# KR-51_V56.net
KiCad netlist of a schematic drawn in Altium Designer
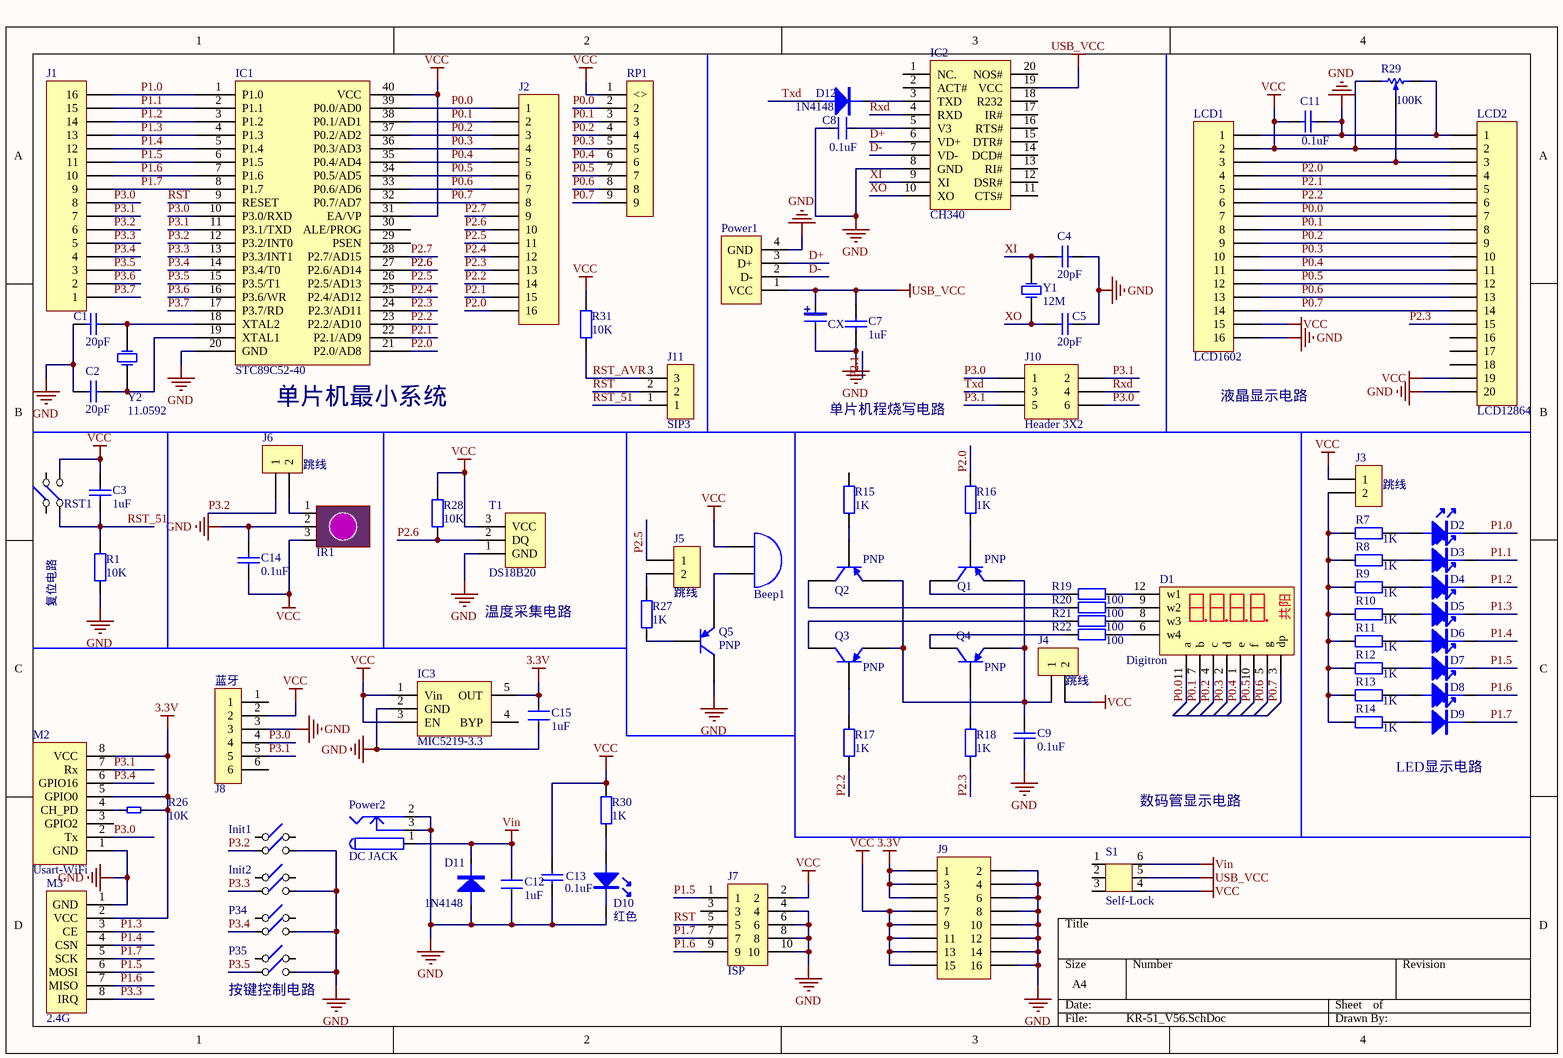
[diagram p0: KR-51_V56.SchDoc]

(export (version "E")
  (design (tool "Eeschema 10.0.6"))
  (components
    (comp (ref "Beep1") (value "蜂鸣器") (footprint "beep") (libsource (lib "声器件") (part "蜂鸣器")))
    (comp (ref "C1")
      (value "20pF")
      (footprint "0805_C")
      (description "Capacitor")
      (fields (field (name "Comment") "Cap_SMT"))
      (libsource (lib "My_Library1") (part "Cap_SMT"))
    )
    (comp (ref "C2")
      (value "20pF")
      (footprint "0805_C")
      (description "Capacitor")
      (fields (field (name "Comment") "Cap_SMT"))
      (libsource (lib "My_Library1") (part "Cap_SMT"))
    )
    (comp (ref "C3")
      (value "1uF")
      (footprint "0805_C")
      (description "Capacitor")
      (fields (field (name "Comment") "Cap_SMT"))
      (libsource (lib "My_Library1") (part "Cap_SMT"))
    )
    (comp (ref "C4")
      (value "20pF")
      (footprint "0805_C")
      (description "Capacitor")
      (fields (field (name "Comment") "Cap_SMT"))
      (libsource (lib "My_Library1") (part "Cap_SMT"))
    )
    (comp (ref "C5")
      (value "20pF")
      (footprint "0805_C")
      (description "Capacitor")
      (fields (field (name "Comment") "Cap_SMT"))
      (libsource (lib "My_Library1") (part "Cap_SMT"))
    )
    (comp (ref "C7")
      (value "1uF")
      (footprint "0805_C")
      (description "Capacitor")
      (fields (field (name "Comment") "Cap_SMT"))
      (libsource (lib "My_Library1") (part "Cap_SMT"))
    )
    (comp (ref "C8")
      (value "0.1uF")
      (footprint "0805C")
      (fields (field (name "Comment") "C0805"))
      (libsource (lib "贴片电容") (part "C0805"))
    )
    (comp (ref "C9")
      (value "0.1uF")
      (footprint "0805_C")
      (description "Capacitor")
      (fields (field (name "Comment") "Cap_SMT"))
      (libsource (lib "My_Library1") (part "Cap_SMT"))
    )
    (comp (ref "C11")
      (value "0.1uF")
      (footprint "0805_C")
      (description "Capacitor")
      (fields (field (name "Comment") "Cap_SMT"))
      (libsource (lib "My_Library1") (part "Cap_SMT"))
    )
    (comp (ref "C12")
      (value "1uF")
      (footprint "0805C")
      (fields (field (name "Comment") "C0805"))
      (libsource (lib "贴片电容") (part "C0805"))
    )
    (comp (ref "C13")
      (value "0.1uF")
      (footprint "0805_C")
      (description "Capacitor")
      (fields (field (name "Comment") "Cap_SMT"))
      (libsource (lib "My_Library1") (part "Cap_SMT"))
    )
    (comp (ref "C14")
      (value "0.1uF")
      (footprint "0805_C")
      (description "Capacitor")
      (fields (field (name "Comment") "Cap_SMT"))
      (libsource (lib "My_Library1") (part "Cap_SMT"))
    )
    (comp (ref "C15")
      (value "1uF")
      (footprint "0805C")
      (fields (field (name "Comment") "C0805"))
      (libsource (lib "贴片电容") (part "C0805"))
    )
    (comp (ref "CX") (value "C1206") (footprint "C1206_C") (libsource (lib "贴片电容") (part "钽电容1206")))
    (comp (ref "D1")
      (value "Digitron")
      (footprint "Ditigron_Pack")
      (libsource (lib "My_Library1") (part "Digitron"))
    )
    (comp (ref "D2") (value "LED0805") (footprint "LED0805") (libsource (lib "光电器件") (part "LED0805")))
    (comp (ref "D3") (value "LED0805") (footprint "LED0805") (libsource (lib "光电器件") (part "LED0805")))
    (comp (ref "D4") (value "LED0805") (footprint "LED0805") (libsource (lib "光电器件") (part "LED0805")))
    (comp (ref "D5") (value "LED0805") (footprint "LED0805") (libsource (lib "光电器件") (part "LED0805")))
    (comp (ref "D6") (value "LED0805") (footprint "LED0805") (libsource (lib "光电器件") (part "LED0805")))
    (comp (ref "D7") (value "LED0805") (footprint "LED0805") (libsource (lib "光电器件") (part "LED0805")))
    (comp (ref "D8") (value "LED0805") (footprint "LED0805") (libsource (lib "光电器件") (part "LED0805")))
    (comp (ref "D9") (value "LED0805") (footprint "LED0805") (libsource (lib "光电器件") (part "LED0805")))
    (comp (ref "D10") (value "红色") (footprint "LED0805") (libsource (lib "光电器件") (part "LED0805")))
    (comp (ref "D11") (value "1N4148") (footprint "0805D") (libsource (lib "贴片二极管") (part "0805D")))
    (comp (ref "D12") (value "1N4148") (footprint "0805D") (libsource (lib "") (part "0805D_1")))
    (comp (ref "IC1")
      (value "STC89C52-40")
      (footprint "DIP_40S")
      (libsource (lib "单片机") (part "STC89C52-40"))
    )
    (comp (ref "IC2") (value "CH340") (footprint "SSOP-20") (libsource (lib "常用芯片") (part "CH340")))
    (comp (ref "IC3")
      (value "MIC5219-3.3")
      (footprint "SOT_23_5")
      (fields (field (name "Comment") "MIC5219_3.3"))
      (libsource (lib "常用芯片") (part "MIC5219_3.3"))
    )
    (comp (ref "Init1") (value "Init0") (footprint "switch key") (libsource (lib "开关") (part "switch")))
    (comp (ref "Init2") (value "Init1") (footprint "switch key") (libsource (lib "开关") (part "switch")))
    (comp (ref "IR1") (value "红外接收头") (footprint "红外接收头-卧") (libsource (lib "传感器") (part "红外接收头")))
    (comp (ref "J1")
      (value "Header 16")
      (footprint "HDR1X16")
      (description "Header, 16-Pin")
      (fields (field (name "PUBLISHER") "Altium Limited"))
      (libsource (lib "Miscellaneous Connectors") (part "Header 16"))
    )
    (comp (ref "J2")
      (value "Header 16")
      (footprint "HDR1X16")
      (description "Header, 16-Pin")
      (fields (field (name "PUBLISHER") "Altium Limited"))
      (libsource (lib "") (part "Header 16_2"))
    )
    (comp (ref "J3") (value "跳线") (footprint "SIP2-0.254") (libsource (lib "") (part "SIP2-0.254_1")))
    (comp (ref "J4") (value "跳线") (footprint "SIP2-0.254") (libsource (lib "插接件") (part "SIP2-0.254")))
    (comp (ref "J5") (value "跳线") (footprint "SIP2-0.254") (libsource (lib "") (part "SIP2-0.254_1")))
    (comp (ref "J6") (value "跳线") (footprint "SIP2-0.254") (libsource (lib "插接件") (part "SIP2-0.254")))
    (comp (ref "J7") (value "ISP") (footprint "ISP") (libsource (lib "插接件") (part "ISP")))
    (comp (ref "J8") (value "蓝牙") (footprint "SIP6-0.254") (libsource (lib "插接件") (part "SIP6-0.254")))
    (comp (ref "J9")
      (value "Header 8X2")
      (footprint "HDR2X8")
      (description "Header, 8-Pin, Dual row")
      (fields (field (name "PUBLISHER") "Altium Limited"))
      (libsource (lib "Miscellaneous Connectors") (part "Header 8X2"))
    )
    (comp (ref "J10")
      (value "Header 3X2")
      (footprint "HDR2X3")
      (description "Header, 3-Pin, Dual row")
      (fields (field (name "PUBLISHER") "Altium Limited"))
      (libsource (lib "Miscellaneous Connectors") (part "Header 3X2"))
    )
    (comp (ref "J11") (value "SIP3") (footprint "SIP3.0-0.254") (libsource (lib "插接件") (part "SIP3.0-0.254")))
    (comp (ref "LCD1")
      (value "LCD1602")
      (footprint "HDR1X16")
      (description "Header, 16-Pin")
      (fields (field (name "PUBLISHER") "Altium Limited"))
      (libsource (lib "") (part "Header 16_1"))
    )
    (comp (ref "LCD2")
      (value "LCD12864")
      (footprint "HDR1X20")
      (description "Header, 20-Pin")
      (fields (field (name "PUBLISHER") "Altium Limited"))
      (libsource (lib "Miscellaneous Connectors") (part "Header 20"))
    )
    (comp (ref "M2")
      (value "Usart-WiFi")
      (footprint "Module_Usart-WiFi")
      (libsource (lib "My_Library1") (part "Module_Usart-WiFi"))
    )
    (comp (ref "M3")
      (value "2.4G")
      (footprint "Module_2.4G")
      (libsource (lib "My_Library1") (part "Module_2.4G"))
    )
    (comp (ref "P34") (value "~") (footprint "switch key") (libsource (lib "开关") (part "switch")))
    (comp (ref "P35") (value "~") (footprint "switch key") (libsource (lib "开关") (part "switch")))
    (comp (ref "Power1") (value "USB-B") (footprint "USB-B") (libsource (lib "插接件") (part "USB-B")))
    (comp (ref "Power2") (value "DC JACK") (footprint "DC JACK") (libsource (lib "插接件") (part "DC JACK")))
    (comp (ref "Q1") (value "PNP") (footprint "SOT-23Q") (libsource (lib "") (part "PNP_1")))
    (comp (ref "Q2") (value "PNP") (footprint "SOT-23Q") (libsource (lib "贴片晶体管") (part "PNP")))
    (comp (ref "Q3") (value "PNP") (footprint "SOT-23Q") (libsource (lib "") (part "PNP_1")))
    (comp (ref "Q4") (value "PNP") (footprint "SOT-23Q") (libsource (lib "") (part "PNP_1")))
    (comp (ref "Q5") (value "PNP") (footprint "SOT-23Q") (libsource (lib "") (part "PNP_1")))
    (comp (ref "R1")
      (value "10K")
      (footprint "0805_R")
      (description "Resistor")
      (fields (field (name "Comment") "Res_SMT"))
      (libsource (lib "") (part "Res_SMT_1"))
    )
    (comp (ref "R7")
      (value "1K")
      (footprint "0805_R")
      (description "Resistor")
      (fields (field (name "Comment") "Res_SMT"))
      (libsource (lib "My_Library1") (part "Res_SMT"))
    )
    (comp (ref "R8")
      (value "1K")
      (footprint "0805_R")
      (description "Resistor")
      (fields (field (name "Comment") "Res_SMT"))
      (libsource (lib "My_Library1") (part "Res_SMT"))
    )
    (comp (ref "R9")
      (value "1K")
      (footprint "0805_R")
      (description "Resistor")
      (fields (field (name "Comment") "Res_SMT"))
      (libsource (lib "My_Library1") (part "Res_SMT"))
    )
    (comp (ref "R10")
      (value "1K")
      (footprint "0805_R")
      (description "Resistor")
      (fields (field (name "Comment") "Res_SMT"))
      (libsource (lib "My_Library1") (part "Res_SMT"))
    )
    (comp (ref "R11")
      (value "1K")
      (footprint "0805_R")
      (description "Resistor")
      (fields (field (name "Comment") "Res_SMT"))
      (libsource (lib "My_Library1") (part "Res_SMT"))
    )
    (comp (ref "R12")
      (value "1K")
      (footprint "0805_R")
      (description "Resistor")
      (fields (field (name "Comment") "Res_SMT"))
      (libsource (lib "My_Library1") (part "Res_SMT"))
    )
    (comp (ref "R13")
      (value "1K")
      (footprint "0805_R")
      (description "Resistor")
      (fields (field (name "Comment") "Res_SMT"))
      (libsource (lib "My_Library1") (part "Res_SMT"))
    )
    (comp (ref "R14")
      (value "1K")
      (footprint "0805_R")
      (description "Resistor")
      (fields (field (name "Comment") "Res_SMT"))
      (libsource (lib "My_Library1") (part "Res_SMT"))
    )
    (comp (ref "R15")
      (value "1K")
      (footprint "0805_R")
      (description "Resistor")
      (fields (field (name "Comment") "Res_SMT"))
      (libsource (lib "") (part "Res_SMT_1"))
    )
    (comp (ref "R16")
      (value "1K")
      (footprint "0805_R")
      (description "Resistor")
      (fields (field (name "Comment") "Res_SMT"))
      (libsource (lib "") (part "Res_SMT_1"))
    )
    (comp (ref "R17")
      (value "1K")
      (footprint "0805_R")
      (description "Resistor")
      (fields (field (name "Comment") "Res_SMT"))
      (libsource (lib "") (part "Res_SMT_1"))
    )
    (comp (ref "R18")
      (value "1K")
      (footprint "0805_R")
      (description "Resistor")
      (fields (field (name "Comment") "Res_SMT"))
      (libsource (lib "") (part "Res_SMT_1"))
    )
    (comp (ref "R19")
      (value "100")
      (footprint "0805_R")
      (description "Resistor")
      (fields (field (name "Comment") "Res_SMT"))
      (libsource (lib "My_Library1") (part "Res_SMT"))
    )
    (comp (ref "R20")
      (value "100")
      (footprint "0805_R")
      (description "Resistor")
      (fields (field (name "Comment") "Res_SMT"))
      (libsource (lib "My_Library1") (part "Res_SMT"))
    )
    (comp (ref "R21")
      (value "100")
      (footprint "0805_R")
      (description "Resistor")
      (fields (field (name "Comment") "Res_SMT"))
      (libsource (lib "My_Library1") (part "Res_SMT"))
    )
    (comp (ref "R22")
      (value "100")
      (footprint "0805_R")
      (description "Resistor")
      (fields (field (name "Comment") "Res_SMT"))
      (libsource (lib "My_Library1") (part "Res_SMT"))
    )
    (comp (ref "R26")
      (value "10K")
      (footprint "R0805")
      (fields (field (name "Comment") "R0805"))
      (libsource (lib "贴片电阻") (part "R0805"))
    )
    (comp (ref "R27")
      (value "1K")
      (footprint "0805_R")
      (description "Resistor")
      (fields (field (name "Comment") "Res_SMT"))
      (libsource (lib "") (part "Res_SMT_1"))
    )
    (comp (ref "R28")
      (value "10K")
      (footprint "0805_R")
      (description "Resistor")
      (fields (field (name "Comment") "Res_SMT"))
      (libsource (lib "") (part "Res_SMT_1"))
    )
    (comp (ref "R29") (value "100K") (footprint "WH06") (libsource (lib "特殊电阻") (part "3362R")))
    (comp (ref "R30")
      (value "1K")
      (footprint "0805_R")
      (description "Resistor")
      (fields (field (name "Comment") "Res_SMT"))
      (libsource (lib "") (part "Res_SMT_2"))
    )
    (comp (ref "R31")
      (value "10K")
      (footprint "0805_R")
      (description "Resistor")
      (fields (field (name "Comment") "Res_SMT"))
      (libsource (lib "") (part "Res_SMT_1"))
    )
    (comp (ref "RP1") (value "排阻9脚") (footprint "R9PIN") (libsource (lib "特殊电阻") (part "排阻9脚")))
    (comp (ref "RST1") (value "switch") (footprint "switch key") (libsource (lib "开关") (part "switch")))
    (comp (ref "S1")
      (value "Self-Lock")
      (footprint "Self-Lock_2.54")
      (libsource (lib "开关") (part "Self-Lock"))
    )
    (comp (ref "T1")
      (value "DS18B20")
      (footprint "T0_92_2.54")
      (libsource (lib "My_Library1") (part "DS18B20"))
    )
    (comp (ref "Y1") (value "12M") (footprint "HC-49S") (libsource (lib "晶振") (part "XTAL")))
    (comp (ref "Y2") (value "11.0592") (footprint "HC-49S") (libsource (lib "晶振") (part "XTAL")))
  )
  (nets
    (net (code "1") (name "/D+") (class "Default")
      (node (ref "IC2") (pin "6") (pinfunction "VD+_6") (pintype "passive"))
      (node (ref "Power1") (pin "3") (pinfunction "D+_3") (pintype "passive"))
    )
    (net (code "2") (name "/D-") (class "Default")
      (node (ref "IC2") (pin "7") (pinfunction "VD-_7") (pintype "passive"))
      (node (ref "Power1") (pin "2") (pinfunction "D-_2") (pintype "passive"))
    )
    (net (code "3") (name "/P0.0") (class "Default")
      (node (ref "D1") (pin "11") (pinfunction "a_11") (pintype "passive"))
      (node (ref "IC1") (pin "39") (pinfunction "P0.0/AD0_39") (pintype "passive"))
      (node (ref "J2") (pin "1") (pinfunction "1_1") (pintype "passive"))
      (node (ref "LCD1") (pin "7") (pinfunction "7_7") (pintype "passive"))
      (node (ref "LCD2") (pin "7") (pinfunction "7_7") (pintype "passive"))
      (node (ref "RP1") (pin "2") (pinfunction "2_2") (pintype "passive"))
    )
    (net (code "4") (name "/P0.1") (class "Default")
      (node (ref "D1") (pin "7") (pinfunction "b_7") (pintype "passive"))
      (node (ref "IC1") (pin "38") (pinfunction "P0.1/AD1_38") (pintype "passive"))
      (node (ref "J2") (pin "2") (pinfunction "2_2") (pintype "passive"))
      (node (ref "LCD1") (pin "8") (pinfunction "8_8") (pintype "passive"))
      (node (ref "LCD2") (pin "8") (pinfunction "8_8") (pintype "passive"))
      (node (ref "RP1") (pin "3") (pinfunction "3_3") (pintype "passive"))
    )
    (net (code "5") (name "/P0.2") (class "Default")
      (node (ref "D1") (pin "4") (pinfunction "c_4") (pintype "passive"))
      (node (ref "IC1") (pin "37") (pinfunction "P0.2/AD2_37") (pintype "passive"))
      (node (ref "J2") (pin "3") (pinfunction "3_3") (pintype "passive"))
      (node (ref "LCD1") (pin "9") (pinfunction "9_9") (pintype "passive"))
      (node (ref "LCD2") (pin "9") (pinfunction "9_9") (pintype "passive"))
      (node (ref "RP1") (pin "4") (pinfunction "4_4") (pintype "passive"))
    )
    (net (code "6") (name "/P0.3") (class "Default")
      (node (ref "D1") (pin "2") (pinfunction "d_2") (pintype "passive"))
      (node (ref "IC1") (pin "36") (pinfunction "P0.3/AD3_36") (pintype "passive"))
      (node (ref "J2") (pin "4") (pinfunction "4_4") (pintype "passive"))
      (node (ref "LCD1") (pin "10") (pinfunction "10_10") (pintype "passive"))
      (node (ref "LCD2") (pin "10") (pinfunction "10_10") (pintype "passive"))
      (node (ref "RP1") (pin "5") (pinfunction "5_5") (pintype "passive"))
    )
    (net (code "7") (name "/P0.4") (class "Default")
      (node (ref "D1") (pin "1") (pinfunction "e_1") (pintype "passive"))
      (node (ref "IC1") (pin "35") (pinfunction "P0.4/AD4_35") (pintype "passive"))
      (node (ref "J2") (pin "5") (pinfunction "5_5") (pintype "passive"))
      (node (ref "LCD1") (pin "11") (pinfunction "11_11") (pintype "passive"))
      (node (ref "LCD2") (pin "11") (pinfunction "11_11") (pintype "passive"))
      (node (ref "RP1") (pin "6") (pinfunction "6_6") (pintype "passive"))
    )
    (net (code "8") (name "/P0.5") (class "Default")
      (node (ref "D1") (pin "10") (pinfunction "f_10") (pintype "passive"))
      (node (ref "IC1") (pin "34") (pinfunction "P0.5/AD5_34") (pintype "passive"))
      (node (ref "J2") (pin "6") (pinfunction "6_6") (pintype "passive"))
      (node (ref "LCD1") (pin "12") (pinfunction "12_12") (pintype "passive"))
      (node (ref "LCD2") (pin "12") (pinfunction "12_12") (pintype "passive"))
      (node (ref "RP1") (pin "7") (pinfunction "7_7") (pintype "passive"))
    )
    (net (code "9") (name "/P0.6") (class "Default")
      (node (ref "D1") (pin "5") (pinfunction "g_5") (pintype "passive"))
      (node (ref "IC1") (pin "33") (pinfunction "P0.6/AD6_33") (pintype "passive"))
      (node (ref "J2") (pin "7") (pinfunction "7_7") (pintype "passive"))
      (node (ref "LCD1") (pin "13") (pinfunction "13_13") (pintype "passive"))
      (node (ref "LCD2") (pin "13") (pinfunction "13_13") (pintype "passive"))
      (node (ref "RP1") (pin "8") (pinfunction "8_8") (pintype "passive"))
    )
    (net (code "10") (name "/P0.7") (class "Default")
      (node (ref "D1") (pin "3") (pinfunction "dp_3") (pintype "passive"))
      (node (ref "IC1") (pin "32") (pinfunction "P0.7/AD7_32") (pintype "passive"))
      (node (ref "J2") (pin "8") (pinfunction "8_8") (pintype "passive"))
      (node (ref "LCD1") (pin "14") (pinfunction "14_14") (pintype "passive"))
      (node (ref "LCD2") (pin "14") (pinfunction "14_14") (pintype "passive"))
      (node (ref "RP1") (pin "9") (pinfunction "9_9") (pintype "passive"))
    )
    (net (code "11") (name "/P1.0") (class "Default")
      (node (ref "D2") (pin "K") (pinfunction "2_K") (pintype "passive"))
      (node (ref "IC1") (pin "1") (pinfunction "P1.0_1") (pintype "passive"))
      (node (ref "J1") (pin "16") (pinfunction "16_16") (pintype "passive"))
    )
    (net (code "12") (name "/P1.1") (class "Default")
      (node (ref "D3") (pin "K") (pinfunction "2_K") (pintype "passive"))
      (node (ref "IC1") (pin "2") (pinfunction "P1.1_2") (pintype "passive"))
      (node (ref "J1") (pin "15") (pinfunction "15_15") (pintype "passive"))
    )
    (net (code "13") (name "/P1.2") (class "Default")
      (node (ref "D4") (pin "K") (pinfunction "2_K") (pintype "passive"))
      (node (ref "IC1") (pin "3") (pinfunction "P1.2_3") (pintype "passive"))
      (node (ref "J1") (pin "14") (pinfunction "14_14") (pintype "passive"))
    )
    (net (code "14") (name "/P1.3") (class "Default")
      (node (ref "D5") (pin "K") (pinfunction "2_K") (pintype "passive"))
      (node (ref "IC1") (pin "4") (pinfunction "P1.3_4") (pintype "passive"))
      (node (ref "J1") (pin "13") (pinfunction "13_13") (pintype "passive"))
      (node (ref "M3") (pin "3") (pinfunction "CE_3") (pintype "passive"))
    )
    (net (code "15") (name "/P1.4") (class "Default")
      (node (ref "D6") (pin "K") (pinfunction "2_K") (pintype "passive"))
      (node (ref "IC1") (pin "5") (pinfunction "P1.4_5") (pintype "passive"))
      (node (ref "J1") (pin "12") (pinfunction "12_12") (pintype "passive"))
      (node (ref "M3") (pin "4") (pinfunction "CSN_4") (pintype "passive"))
    )
    (net (code "16") (name "/P1.5") (class "Default")
      (node (ref "D7") (pin "K") (pinfunction "2_K") (pintype "passive"))
      (node (ref "IC1") (pin "6") (pinfunction "P1.5_6") (pintype "passive"))
      (node (ref "J1") (pin "11") (pinfunction "11_11") (pintype "passive"))
      (node (ref "J7") (pin "1") (pinfunction "1_1") (pintype "passive"))
      (node (ref "M3") (pin "6") (pinfunction "MOSI_6") (pintype "passive"))
    )
    (net (code "17") (name "/P1.6") (class "Default")
      (node (ref "D8") (pin "K") (pinfunction "2_K") (pintype "passive"))
      (node (ref "IC1") (pin "7") (pinfunction "P1.6_7") (pintype "passive"))
      (node (ref "J1") (pin "10") (pinfunction "10_10") (pintype "passive"))
      (node (ref "J7") (pin "9") (pinfunction "9_9") (pintype "passive"))
      (node (ref "M3") (pin "7") (pinfunction "MISO_7") (pintype "passive"))
    )
    (net (code "18") (name "/P1.7") (class "Default")
      (node (ref "D9") (pin "K") (pinfunction "2_K") (pintype "passive"))
      (node (ref "IC1") (pin "8") (pinfunction "P1.7_8") (pintype "passive"))
      (node (ref "J1") (pin "9") (pinfunction "9_9") (pintype "passive"))
      (node (ref "J7") (pin "7") (pinfunction "7_7") (pintype "passive"))
      (node (ref "M3") (pin "5") (pinfunction "SCK_5") (pintype "passive"))
    )
    (net (code "19") (name "/P2.0") (class "Default")
      (node (ref "IC1") (pin "21") (pinfunction "P2.0/AD8_21") (pintype "passive"))
      (node (ref "J2") (pin "16") (pinfunction "16_16") (pintype "passive"))
      (node (ref "LCD1") (pin "4") (pinfunction "4_4") (pintype "passive"))
      (node (ref "LCD2") (pin "4") (pinfunction "4_4") (pintype "passive"))
      (node (ref "R16") (pin "2") (pinfunction "2_2") (pintype "passive"))
    )
    (net (code "20") (name "/P2.1") (class "Default")
      (node (ref "IC1") (pin "22") (pinfunction "P2.1/AD9_22") (pintype "passive"))
      (node (ref "J2") (pin "15") (pinfunction "15_15") (pintype "passive"))
      (node (ref "LCD1") (pin "5") (pinfunction "5_5") (pintype "passive"))
      (node (ref "LCD2") (pin "5") (pinfunction "5_5") (pintype "passive"))
    )
    (net (code "21") (name "/P2.2") (class "Default")
      (node (ref "IC1") (pin "23") (pinfunction "P2.2/AD10_23") (pintype "passive"))
      (node (ref "J2") (pin "14") (pinfunction "14_14") (pintype "passive"))
      (node (ref "LCD1") (pin "6") (pinfunction "6_6") (pintype "passive"))
      (node (ref "LCD2") (pin "6") (pinfunction "6_6") (pintype "passive"))
      (node (ref "R17") (pin "1") (pinfunction "1_1") (pintype "passive"))
    )
    (net (code "22") (name "/P2.3") (class "Default")
      (node (ref "IC1") (pin "24") (pinfunction "P2.3/AD11_24") (pintype "passive"))
      (node (ref "J2") (pin "13") (pinfunction "13_13") (pintype "passive"))
      (node (ref "LCD2") (pin "15") (pinfunction "15_15") (pintype "passive"))
      (node (ref "R18") (pin "1") (pinfunction "1_1") (pintype "passive"))
    )
    (net (code "23") (name "/P2.4") (class "Default")
      (node (ref "IC1") (pin "25") (pinfunction "P2.4/AD12_25") (pintype "passive"))
      (node (ref "J2") (pin "12") (pinfunction "12_12") (pintype "passive"))
    )
    (net (code "24") (name "/P2.5") (class "Default")
      (node (ref "IC1") (pin "26") (pinfunction "P2.5/AD13_26") (pintype "passive"))
      (node (ref "J2") (pin "11") (pinfunction "11_11") (pintype "passive"))
      (node (ref "J5") (pin "1") (pinfunction "1_1") (pintype "passive"))
    )
    (net (code "25") (name "/P2.6") (class "Default")
      (node (ref "IC1") (pin "27") (pinfunction "P2.6/AD14_27") (pintype "passive"))
      (node (ref "J2") (pin "10") (pinfunction "10_10") (pintype "passive"))
      (node (ref "R28") (pin "1") (pinfunction "1_1") (pintype "passive"))
      (node (ref "T1") (pin "2") (pinfunction "DQ_2") (pintype "passive"))
    )
    (net (code "26") (name "/P2.7") (class "Default")
      (node (ref "IC1") (pin "28") (pinfunction "P2.7/AD15_28") (pintype "passive"))
      (node (ref "J2") (pin "9") (pinfunction "9_9") (pintype "passive"))
    )
    (net (code "27") (name "/P3.0") (class "Default")
      (node (ref "IC1") (pin "10") (pinfunction "P3.0/RXD_10") (pintype "passive"))
      (node (ref "J1") (pin "8") (pinfunction "8_8") (pintype "passive"))
      (node (ref "J10") (pin "1") (pinfunction "1_1") (pintype "passive"))
      (node (ref "J10") (pin "6") (pinfunction "6_6") (pintype "passive"))
      (node (ref "J8") (pin "4") (pinfunction "4_4") (pintype "passive"))
      (node (ref "M2") (pin "2") (pinfunction "Tx_2") (pintype "passive"))
    )
    (net (code "28") (name "/P3.1") (class "Default")
      (node (ref "IC1") (pin "11") (pinfunction "P3.1/TXD_11") (pintype "passive"))
      (node (ref "J1") (pin "7") (pinfunction "7_7") (pintype "passive"))
      (node (ref "J10") (pin "2") (pinfunction "2_2") (pintype "passive"))
      (node (ref "J10") (pin "5") (pinfunction "5_5") (pintype "passive"))
      (node (ref "J8") (pin "5") (pinfunction "5_5") (pintype "passive"))
      (node (ref "M2") (pin "7") (pinfunction "Rx_7") (pintype "passive"))
    )
    (net (code "29") (name "/P3.2") (class "Default")
      (node (ref "IC1") (pin "12") (pinfunction "P3.2/INT0_12") (pintype "passive"))
      (node (ref "Init1") (pin "1") (pinfunction "COMMON_1") (pintype "passive"))
      (node (ref "J1") (pin "6") (pinfunction "6_6") (pintype "passive"))
      (node (ref "J6") (pin "1") (pinfunction "1_1") (pintype "passive"))
    )
    (net (code "30") (name "/P3.3") (class "Default")
      (node (ref "IC1") (pin "13") (pinfunction "P3.3/INT1_13") (pintype "passive"))
      (node (ref "Init2") (pin "1") (pinfunction "COMMON_1") (pintype "passive"))
      (node (ref "J1") (pin "5") (pinfunction "5_5") (pintype "passive"))
      (node (ref "M3") (pin "8") (pinfunction "IRQ_8") (pintype "passive"))
    )
    (net (code "31") (name "/P3.4") (class "Default")
      (node (ref "IC1") (pin "14") (pinfunction "P3.4/T0_14") (pintype "passive"))
      (node (ref "J1") (pin "4") (pinfunction "4_4") (pintype "passive"))
      (node (ref "M2") (pin "6") (pinfunction "GPIO16_6") (pintype "passive"))
      (node (ref "P34") (pin "1") (pinfunction "COMMON_1") (pintype "passive"))
    )
    (net (code "32") (name "/P3.5") (class "Default")
      (node (ref "IC1") (pin "15") (pinfunction "P3.5/T1_15") (pintype "passive"))
      (node (ref "J1") (pin "3") (pinfunction "3_3") (pintype "passive"))
      (node (ref "P35") (pin "1") (pinfunction "COMMON_1") (pintype "passive"))
    )
    (net (code "33") (name "/P3.6") (class "Default")
      (node (ref "IC1") (pin "16") (pinfunction "P3.6/WR_16") (pintype "passive"))
      (node (ref "J1") (pin "2") (pinfunction "2_2") (pintype "passive"))
    )
    (net (code "34") (name "/P3.7") (class "Default")
      (node (ref "IC1") (pin "17") (pinfunction "P3.7/RD_17") (pintype "passive"))
      (node (ref "J1") (pin "1") (pinfunction "1_1") (pintype "passive"))
    )
    (net (code "35") (name "/RST") (class "Default")
      (node (ref "IC1") (pin "9") (pinfunction "RESET_9") (pintype "passive"))
      (node (ref "J11") (pin "2") (pinfunction "2_2") (pintype "passive"))
      (node (ref "J7") (pin "5") (pinfunction "5_5") (pintype "passive"))
    )
    (net (code "36") (name "/RST_51") (class "Default")
      (node (ref "C3") (pin "2") (pinfunction "2_2") (pintype "passive"))
      (node (ref "J11") (pin "1") (pinfunction "1_1") (pintype "passive"))
      (node (ref "R1") (pin "2") (pinfunction "2_2") (pintype "passive"))
      (node (ref "RST1") (pin "1") (pinfunction "COMMON_1") (pintype "passive"))
    )
    (net (code "37") (name "/RST_AVR") (class "Default")
      (node (ref "J11") (pin "3") (pinfunction "3_3") (pintype "passive"))
      (node (ref "R31") (pin "1") (pinfunction "1_1") (pintype "passive"))
    )
    (net (code "38") (name "/Rxd") (class "Default")
      (node (ref "IC2") (pin "4") (pinfunction "RXD_4") (pintype "passive"))
      (node (ref "J10") (pin "4") (pinfunction "4_4") (pintype "passive"))
    )
    (net (code "39") (name "/Txd") (class "Default")
      (node (ref "D12") (pin "A") (pinfunction "1_A") (pintype "passive"))
      (node (ref "J10") (pin "3") (pinfunction "3_3") (pintype "passive"))
    )
    (net (code "40") (name "/XI") (class "Default")
      (node (ref "C4") (pin "1") (pinfunction "1_1") (pintype "passive"))
      (node (ref "IC2") (pin "9") (pinfunction "XI_9") (pintype "passive"))
      (node (ref "Y1") (pin "2") (pinfunction "2_2") (pintype "passive"))
    )
    (net (code "41") (name "/XO") (class "Default")
      (node (ref "C5") (pin "1") (pinfunction "1_1") (pintype "passive"))
      (node (ref "IC2") (pin "10") (pinfunction "XO_10") (pintype "passive"))
      (node (ref "Y1") (pin "1") (pinfunction "1_1") (pintype "passive"))
    )
    (net (code "42") (name "3.3V") (class "Default")
      (node (ref "C15") (pin "1") (pinfunction "1_1") (pintype "passive"))
      (node (ref "IC3") (pin "5") (pinfunction "OUT_5") (pintype "passive"))
      (node (ref "J9") (pin "1") (pinfunction "1_1") (pintype "passive"))
      (node (ref "J9") (pin "3") (pinfunction "3_3") (pintype "passive"))
      (node (ref "J9") (pin "5") (pinfunction "5_5") (pintype "passive"))
      (node (ref "M2") (pin "5") (pinfunction "GPIO0_5") (pintype "passive"))
      (node (ref "M2") (pin "8") (pinfunction "VCC_8") (pintype "passive"))
      (node (ref "M3") (pin "2") (pinfunction "VCC_2") (pintype "passive"))
      (node (ref "R26") (pin "2") (pinfunction "2_2") (pintype "passive"))
    )
    (net (code "43") (name "GND") (class "Default")
      (node (ref "C1") (pin "2") (pinfunction "2_2") (pintype "passive"))
      (node (ref "C11") (pin "2") (pinfunction "2_2") (pintype "passive"))
      (node (ref "C12") (pin "2") (pinfunction "2_2") (pintype "passive"))
      (node (ref "C13") (pin "1") (pinfunction "1_1") (pintype "passive"))
      (node (ref "C14") (pin "2") (pinfunction "2_2") (pintype "passive"))
      (node (ref "C15") (pin "2") (pinfunction "2_2") (pintype "passive"))
      (node (ref "C2") (pin "2") (pinfunction "2_2") (pintype "passive"))
      (node (ref "C4") (pin "2") (pinfunction "2_2") (pintype "passive"))
      (node (ref "C5") (pin "2") (pinfunction "2_2") (pintype "passive"))
      (node (ref "C7") (pin "2") (pinfunction "2_2") (pintype "passive"))
      (node (ref "C8") (pin "1") (pinfunction "1_1") (pintype "passive"))
      (node (ref "C9") (pin "1") (pinfunction "1_1") (pintype "passive"))
      (node (ref "CX") (pin "2") (pinfunction "2_2") (pintype "passive"))
      (node (ref "D10") (pin "K") (pinfunction "2_K") (pintype "passive"))
      (node (ref "D11") (pin "A") (pinfunction "1_A") (pintype "passive"))
      (node (ref "IC1") (pin "20") (pinfunction "GND_20") (pintype "passive"))
      (node (ref "IC2") (pin "8") (pinfunction "GND_8") (pintype "passive"))
      (node (ref "IC3") (pin "2") (pinfunction "GND_2") (pintype "passive"))
      (node (ref "IR1") (pin "2") (pinfunction "GND_2") (pintype "passive"))
      (node (ref "Init1") (pin "2") (pinfunction "NO_2") (pintype "passive"))
      (node (ref "Init2") (pin "2") (pinfunction "NO_2") (pintype "passive"))
      (node (ref "J7") (pin "10") (pinfunction "10_10") (pintype "passive"))
      (node (ref "J7") (pin "4") (pinfunction "4_4") (pintype "passive"))
      (node (ref "J7") (pin "6") (pinfunction "6_6") (pintype "passive"))
      (node (ref "J7") (pin "8") (pinfunction "8_8") (pintype "passive"))
      (node (ref "J8") (pin "3") (pinfunction "3_3") (pintype "passive"))
      (node (ref "J9") (pin "10") (pinfunction "10_10") (pintype "passive"))
      (node (ref "J9") (pin "12") (pinfunction "12_12") (pintype "passive"))
      (node (ref "J9") (pin "14") (pinfunction "14_14") (pintype "passive"))
      (node (ref "J9") (pin "16") (pinfunction "16_16") (pintype "passive"))
      (node (ref "J9") (pin "2") (pinfunction "2_2") (pintype "passive"))
      (node (ref "J9") (pin "4") (pinfunction "4_4") (pintype "passive"))
      (node (ref "J9") (pin "6") (pinfunction "6_6") (pintype "passive"))
      (node (ref "J9") (pin "8") (pinfunction "8_8") (pintype "passive"))
      (node (ref "LCD1") (pin "1") (pinfunction "1_1") (pintype "passive"))
      (node (ref "LCD1") (pin "16") (pinfunction "16_16") (pintype "passive"))
      (node (ref "LCD2") (pin "1") (pinfunction "1_1") (pintype "passive"))
      (node (ref "LCD2") (pin "20") (pinfunction "20_20") (pintype "passive"))
      (node (ref "M2") (pin "1") (pinfunction "GND_1") (pintype "passive"))
      (node (ref "M3") (pin "1") (pinfunction "GND_1") (pintype "passive"))
      (node (ref "P34") (pin "2") (pinfunction "NO_2") (pintype "passive"))
      (node (ref "P35") (pin "2") (pinfunction "NO_2") (pintype "passive"))
      (node (ref "Power1") (pin "4") (pinfunction "GND_4") (pintype "passive"))
      (node (ref "Power2") (pin "2") (pinfunction "2_2") (pintype "power_in"))
      (node (ref "Power2") (pin "3") (pinfunction "3_3") (pintype "power_in"))
      (node (ref "Q5") (pin "C") (pinfunction "C_C") (pintype "passive"))
      (node (ref "R1") (pin "1") (pinfunction "1_1") (pintype "passive"))
      (node (ref "R29") (pin "3") (pinfunction "3_3") (pintype "passive"))
      (node (ref "T1") (pin "1") (pinfunction "GND_1") (pintype "passive"))
    )
    (net (code "44") (name "Net-(Beep1-A)") (class "Default")
      (node (ref "Beep1") (pin "1") (pinfunction "A_1") (pintype "passive"))
      (node (ref "Q5") (pin "E") (pinfunction "E_E") (pintype "passive"))
    )
    (net (code "45") (name "Net-(C9-Pad2)") (class "Default")
      (node (ref "C9") (pin "2") (pinfunction "2_2") (pintype "passive"))
      (node (ref "J4") (pin "1") (pinfunction "1_1") (pintype "passive"))
      (node (ref "Q1") (pin "E") (pinfunction "E_E") (pintype "passive"))
      (node (ref "Q2") (pin "E") (pinfunction "E_E") (pintype "passive"))
      (node (ref "Q3") (pin "E") (pinfunction "E_E") (pintype "passive"))
      (node (ref "Q4") (pin "E") (pinfunction "E_E") (pintype "passive"))
    )
    (net (code "46") (name "Net-(D1-w1)") (class "Default")
      (node (ref "D1") (pin "12") (pinfunction "w1_12") (pintype "passive"))
      (node (ref "R19") (pin "2") (pinfunction "2_2") (pintype "passive"))
    )
    (net (code "47") (name "Net-(D1-w2)") (class "Default")
      (node (ref "D1") (pin "9") (pinfunction "w2_9") (pintype "passive"))
      (node (ref "R20") (pin "2") (pinfunction "2_2") (pintype "passive"))
    )
    (net (code "48") (name "Net-(D1-w3)") (class "Default")
      (node (ref "D1") (pin "8") (pinfunction "w3_8") (pintype "passive"))
      (node (ref "R21") (pin "2") (pinfunction "2_2") (pintype "passive"))
    )
    (net (code "49") (name "Net-(D1-w4)") (class "Default")
      (node (ref "D1") (pin "6") (pinfunction "w4_6") (pintype "passive"))
      (node (ref "R22") (pin "2") (pinfunction "2_2") (pintype "passive"))
    )
    (net (code "50") (name "Net-(D2-1)") (class "Default")
      (node (ref "D2") (pin "A") (pinfunction "1_A") (pintype "passive"))
      (node (ref "R7") (pin "2") (pinfunction "2_2") (pintype "passive"))
    )
    (net (code "51") (name "Net-(D3-1)") (class "Default")
      (node (ref "D3") (pin "A") (pinfunction "1_A") (pintype "passive"))
      (node (ref "R8") (pin "2") (pinfunction "2_2") (pintype "passive"))
    )
    (net (code "52") (name "Net-(D4-1)") (class "Default")
      (node (ref "D4") (pin "A") (pinfunction "1_A") (pintype "passive"))
      (node (ref "R9") (pin "2") (pinfunction "2_2") (pintype "passive"))
    )
    (net (code "53") (name "Net-(D5-1)") (class "Default")
      (node (ref "D5") (pin "A") (pinfunction "1_A") (pintype "passive"))
      (node (ref "R10") (pin "2") (pinfunction "2_2") (pintype "passive"))
    )
    (net (code "54") (name "Net-(D6-1)") (class "Default")
      (node (ref "D6") (pin "A") (pinfunction "1_A") (pintype "passive"))
      (node (ref "R11") (pin "2") (pinfunction "2_2") (pintype "passive"))
    )
    (net (code "55") (name "Net-(D7-1)") (class "Default")
      (node (ref "D7") (pin "A") (pinfunction "1_A") (pintype "passive"))
      (node (ref "R12") (pin "2") (pinfunction "2_2") (pintype "passive"))
    )
    (net (code "56") (name "Net-(D8-1)") (class "Default")
      (node (ref "D8") (pin "A") (pinfunction "1_A") (pintype "passive"))
      (node (ref "R13") (pin "2") (pinfunction "2_2") (pintype "passive"))
    )
    (net (code "57") (name "Net-(D9-1)") (class "Default")
      (node (ref "D9") (pin "A") (pinfunction "1_A") (pintype "passive"))
      (node (ref "R14") (pin "2") (pinfunction "2_2") (pintype "passive"))
    )
    (net (code "58") (name "Net-(D10-1)") (class "Default")
      (node (ref "D10") (pin "A") (pinfunction "1_A") (pintype "passive"))
      (node (ref "R30") (pin "2") (pinfunction "2_2") (pintype "passive"))
    )
    (net (code "59") (name "Net-(D12-2)") (class "Default")
      (node (ref "D12") (pin "K") (pinfunction "2_K") (pintype "passive"))
      (node (ref "IC2") (pin "3") (pinfunction "TXD_3") (pintype "passive"))
    )
    (net (code "60") (name "Net-(IC1-XTAL1)") (class "Default")
      (node (ref "C2") (pin "1") (pinfunction "1_1") (pintype "passive"))
      (node (ref "IC1") (pin "19") (pinfunction "XTAL1_19") (pintype "passive"))
      (node (ref "Y2") (pin "2") (pinfunction "2_2") (pintype "passive"))
    )
    (net (code "61") (name "Net-(IC1-XTAL2)") (class "Default")
      (node (ref "C1") (pin "1") (pinfunction "1_1") (pintype "passive"))
      (node (ref "IC1") (pin "18") (pinfunction "XTAL2_18") (pintype "passive"))
      (node (ref "Y2") (pin "1") (pinfunction "1_1") (pintype "passive"))
    )
    (net (code "62") (name "Net-(IC2-V3)") (class "Default")
      (node (ref "C8") (pin "2") (pinfunction "2_2") (pintype "passive"))
      (node (ref "IC2") (pin "5") (pinfunction "V3_5") (pintype "passive"))
    )
    (net (code "63") (name "Net-(IR1-IN)") (class "Default")
      (node (ref "IR1") (pin "1") (pinfunction "IN_1") (pintype "passive"))
      (node (ref "J6") (pin "2") (pinfunction "2_2") (pintype "passive"))
    )
    (net (code "64") (name "Net-(J3-Pad2)") (class "Default")
      (node (ref "J3") (pin "2") (pinfunction "2_2") (pintype "passive"))
      (node (ref "R10") (pin "1") (pinfunction "1_1") (pintype "passive"))
      (node (ref "R11") (pin "1") (pinfunction "1_1") (pintype "passive"))
      (node (ref "R12") (pin "1") (pinfunction "1_1") (pintype "passive"))
      (node (ref "R13") (pin "1") (pinfunction "1_1") (pintype "passive"))
      (node (ref "R14") (pin "1") (pinfunction "1_1") (pintype "passive"))
      (node (ref "R7") (pin "1") (pinfunction "1_1") (pintype "passive"))
      (node (ref "R8") (pin "1") (pinfunction "1_1") (pintype "passive"))
      (node (ref "R9") (pin "1") (pinfunction "1_1") (pintype "passive"))
    )
    (net (code "65") (name "Net-(J5-Pad2)") (class "Default")
      (node (ref "J5") (pin "2") (pinfunction "2_2") (pintype "passive"))
      (node (ref "R27") (pin "2") (pinfunction "2_2") (pintype "passive"))
    )
    (net (code "66") (name "Net-(LCD1-Pad3)") (class "Default")
      (node (ref "LCD1") (pin "3") (pinfunction "3_3") (pintype "passive"))
      (node (ref "LCD2") (pin "3") (pinfunction "3_3") (pintype "passive"))
      (node (ref "R29") (pin "2") (pinfunction "2_2") (pintype "passive"))
    )
    (net (code "67") (name "Net-(M2-CH_PD)") (class "Default")
      (node (ref "M2") (pin "4") (pinfunction "CH_PD_4") (pintype "passive"))
      (node (ref "R26") (pin "1") (pinfunction "1_1") (pintype "passive"))
    )
    (net (code "68") (name "Net-(Q1-PadB)") (class "Default")
      (node (ref "Q1") (pin "B") (pinfunction "B_B") (pintype "passive"))
      (node (ref "R16") (pin "1") (pinfunction "1_1") (pintype "passive"))
    )
    (net (code "69") (name "Net-(Q1-PadC)") (class "Default")
      (node (ref "Q1") (pin "C") (pinfunction "C_C") (pintype "passive"))
      (node (ref "R19") (pin "1") (pinfunction "1_1") (pintype "passive"))
    )
    (net (code "70") (name "Net-(Q2-PadB)") (class "Default")
      (node (ref "Q2") (pin "B") (pinfunction "B_B") (pintype "passive"))
      (node (ref "R15") (pin "1") (pinfunction "1_1") (pintype "passive"))
    )
    (net (code "71") (name "Net-(Q2-PadC)") (class "Default")
      (node (ref "Q2") (pin "C") (pinfunction "C_C") (pintype "passive"))
      (node (ref "R20") (pin "1") (pinfunction "1_1") (pintype "passive"))
    )
    (net (code "72") (name "Net-(Q3-PadB)") (class "Default")
      (node (ref "Q3") (pin "B") (pinfunction "B_B") (pintype "passive"))
      (node (ref "R17") (pin "2") (pinfunction "2_2") (pintype "passive"))
    )
    (net (code "73") (name "Net-(Q3-PadC)") (class "Default")
      (node (ref "Q3") (pin "C") (pinfunction "C_C") (pintype "passive"))
      (node (ref "R21") (pin "1") (pinfunction "1_1") (pintype "passive"))
    )
    (net (code "74") (name "Net-(Q4-PadB)") (class "Default")
      (node (ref "Q4") (pin "B") (pinfunction "B_B") (pintype "passive"))
      (node (ref "R18") (pin "2") (pinfunction "2_2") (pintype "passive"))
    )
    (net (code "75") (name "Net-(Q4-PadC)") (class "Default")
      (node (ref "Q4") (pin "C") (pinfunction "C_C") (pintype "passive"))
      (node (ref "R22") (pin "1") (pinfunction "1_1") (pintype "passive"))
    )
    (net (code "76") (name "Net-(Q5-PadB)") (class "Default")
      (node (ref "Q5") (pin "B") (pinfunction "B_B") (pintype "passive"))
      (node (ref "R27") (pin "1") (pinfunction "1_1") (pintype "passive"))
    )
    (net (code "77") (name "USB_VCC") (class "Default")
      (node (ref "C7") (pin "1") (pinfunction "1_1") (pintype "passive"))
      (node (ref "CX") (pin "1") (pinfunction "1_1") (pintype "passive"))
      (node (ref "IC2") (pin "19") (pinfunction "VCC_19") (pintype "power_in"))
      (node (ref "Power1") (pin "1") (pinfunction "VCC_1") (pintype "passive"))
      (node (ref "S1") (pin "5") (pinfunction "5_5") (pintype "passive"))
    )
    (net (code "78") (name "VCC") (class "Default")
      (node (ref "Beep1") (pin "2") (pinfunction "B_2") (pintype "passive"))
      (node (ref "C11") (pin "1") (pinfunction "1_1") (pintype "passive"))
      (node (ref "C13") (pin "2") (pinfunction "2_2") (pintype "passive"))
      (node (ref "C14") (pin "1") (pinfunction "1_1") (pintype "passive"))
      (node (ref "C3") (pin "1") (pinfunction "1_1") (pintype "passive"))
      (node (ref "IC1") (pin "31") (pinfunction "EA/VP_31") (pintype "passive"))
      (node (ref "IC1") (pin "40") (pinfunction "VCC_40") (pintype "passive"))
      (node (ref "IC3") (pin "1") (pinfunction "Vin_1") (pintype "passive"))
      (node (ref "IC3") (pin "3") (pinfunction "EN_3") (pintype "passive"))
      (node (ref "IR1") (pin "3") (pinfunction "VCC_3") (pintype "passive"))
      (node (ref "J3") (pin "1") (pinfunction "1_1") (pintype "passive"))
      (node (ref "J4") (pin "2") (pinfunction "2_2") (pintype "passive"))
      (node (ref "J7") (pin "2") (pinfunction "2_2") (pintype "passive"))
      (node (ref "J8") (pin "2") (pinfunction "2_2") (pintype "passive"))
      (node (ref "J9") (pin "11") (pinfunction "11_11") (pintype "passive"))
      (node (ref "J9") (pin "13") (pinfunction "13_13") (pintype "passive"))
      (node (ref "J9") (pin "15") (pinfunction "15_15") (pintype "passive"))
      (node (ref "J9") (pin "7") (pinfunction "7_7") (pintype "passive"))
      (node (ref "J9") (pin "9") (pinfunction "9_9") (pintype "passive"))
      (node (ref "LCD1") (pin "15") (pinfunction "15_15") (pintype "passive"))
      (node (ref "LCD1") (pin "2") (pinfunction "2_2") (pintype "passive"))
      (node (ref "LCD2") (pin "19") (pinfunction "19_19") (pintype "passive"))
      (node (ref "LCD2") (pin "2") (pinfunction "2_2") (pintype "passive"))
      (node (ref "R28") (pin "2") (pinfunction "2_2") (pintype "passive"))
      (node (ref "R29") (pin "1") (pinfunction "1_1") (pintype "passive"))
      (node (ref "R30") (pin "1") (pinfunction "1_1") (pintype "passive"))
      (node (ref "R31") (pin "2") (pinfunction "2_2") (pintype "passive"))
      (node (ref "RP1") (pin "1") (pinfunction "<>_1") (pintype "passive"))
      (node (ref "RST1") (pin "2") (pinfunction "NO_2") (pintype "passive"))
      (node (ref "S1") (pin "4") (pinfunction "4_4") (pintype "passive"))
      (node (ref "T1") (pin "3") (pinfunction "VCC_3") (pintype "passive"))
    )
    (net (code "79") (name "Vin") (class "Default")
      (node (ref "C12") (pin "1") (pinfunction "1_1") (pintype "passive"))
      (node (ref "D11") (pin "K") (pinfunction "2_K") (pintype "passive"))
      (node (ref "Power2") (pin "1") (pinfunction "1_1") (pintype "power_in"))
      (node (ref "S1") (pin "6") (pinfunction "6_6") (pintype "passive"))
    )
    (net (code "80") (name "unconnected-(IC1-ALE{slash}PROG-Pad30)") (class "Default")
      (node (ref "IC1") (pin "30") (pinfunction "ALE/PROG_30") (pintype "passive"))
    )
    (net (code "81") (name "unconnected-(IC1-PSEN-Pad29)") (class "Default")
      (node (ref "IC1") (pin "29") (pinfunction "PSEN_29") (pintype "passive"))
    )
    (net (code "82") (name "unconnected-(IC2-ACT#-Pad2)") (class "Default")
      (node (ref "IC2") (pin "2") (pinfunction "ACT#_2") (pintype "passive"))
    )
    (net (code "83") (name "unconnected-(IC2-CTS#-Pad11)") (class "Default")
      (node (ref "IC2") (pin "11") (pinfunction "CTS#_11") (pintype "passive"))
    )
    (net (code "84") (name "unconnected-(IC2-DCD#-Pad14)") (class "Default")
      (node (ref "IC2") (pin "14") (pinfunction "DCD#_14") (pintype "passive"))
    )
    (net (code "85") (name "unconnected-(IC2-DSR#-Pad12)") (class "Default")
      (node (ref "IC2") (pin "12") (pinfunction "DSR#_12") (pintype "passive"))
    )
    (net (code "86") (name "unconnected-(IC2-DTR#-Pad15)") (class "Default")
      (node (ref "IC2") (pin "15") (pinfunction "DTR#_15") (pintype "passive"))
    )
    (net (code "87") (name "unconnected-(IC2-IR#-Pad17)") (class "Default")
      (node (ref "IC2") (pin "17") (pinfunction "IR#_17") (pintype "power_in"))
    )
    (net (code "88") (name "unconnected-(IC2-NC.-Pad1)") (class "Default")
      (node (ref "IC2") (pin "1") (pinfunction "NC._1") (pintype "passive"))
    )
    (net (code "89") (name "unconnected-(IC2-NOS#-Pad20)") (class "Default")
      (node (ref "IC2") (pin "20") (pinfunction "NOS#_20") (pintype "power_in"))
    )
    (net (code "90") (name "unconnected-(IC2-R232-Pad18)") (class "Default")
      (node (ref "IC2") (pin "18") (pinfunction "R232_18") (pintype "power_in"))
    )
    (net (code "91") (name "unconnected-(IC2-RI#-Pad13)") (class "Default")
      (node (ref "IC2") (pin "13") (pinfunction "RI#_13") (pintype "passive"))
    )
    (net (code "92") (name "unconnected-(IC2-RTS#-Pad16)") (class "Default")
      (node (ref "IC2") (pin "16") (pinfunction "RTS#_16") (pintype "passive"))
    )
    (net (code "93") (name "unconnected-(IC3-BYP-Pad4)") (class "Default")
      (node (ref "IC3") (pin "4") (pinfunction "BYP_4") (pintype "passive"))
    )
    (net (code "94") (name "unconnected-(Init1-COMMON-Pad1)") (class "Default")
      (node (ref "Init1") (pin "1") (pinfunction "COMMON_1") (pintype "passive"))
    )
    (net (code "95") (name "unconnected-(Init1-NO-Pad2)") (class "Default")
      (node (ref "Init1") (pin "2") (pinfunction "NO_2") (pintype "passive"))
    )
    (net (code "96") (name "unconnected-(Init2-COMMON-Pad1)") (class "Default")
      (node (ref "Init2") (pin "1") (pinfunction "COMMON_1") (pintype "passive"))
    )
    (net (code "97") (name "unconnected-(Init2-NO-Pad2)") (class "Default")
      (node (ref "Init2") (pin "2") (pinfunction "NO_2") (pintype "passive"))
    )
    (net (code "98") (name "unconnected-(J7-Pad3)") (class "Default")
      (node (ref "J7") (pin "3") (pinfunction "3_3") (pintype "passive"))
    )
    (net (code "99") (name "unconnected-(J8-Pad1)") (class "Default")
      (node (ref "J8") (pin "1") (pinfunction "1_1") (pintype "passive"))
    )
    (net (code "100") (name "unconnected-(J8-Pad6)") (class "Default")
      (node (ref "J8") (pin "6") (pinfunction "6_6") (pintype "passive"))
    )
    (net (code "101") (name "unconnected-(LCD2-Pad16)") (class "Default")
      (node (ref "LCD2") (pin "16") (pinfunction "16_16") (pintype "passive"))
    )
    (net (code "102") (name "unconnected-(LCD2-Pad17)") (class "Default")
      (node (ref "LCD2") (pin "17") (pinfunction "17_17") (pintype "passive"))
    )
    (net (code "103") (name "unconnected-(LCD2-Pad18)") (class "Default")
      (node (ref "LCD2") (pin "18") (pinfunction "18_18") (pintype "passive"))
    )
    (net (code "104") (name "unconnected-(M2-GPIO2-Pad3)") (class "Default")
      (node (ref "M2") (pin "3") (pinfunction "GPIO2_3") (pintype "passive"))
    )
    (net (code "105") (name "unconnected-(P34-COMMON-Pad1)") (class "Default")
      (node (ref "P34") (pin "1") (pinfunction "COMMON_1") (pintype "passive"))
    )
    (net (code "106") (name "unconnected-(P34-NO-Pad2)") (class "Default")
      (node (ref "P34") (pin "2") (pinfunction "NO_2") (pintype "passive"))
    )
    (net (code "107") (name "unconnected-(P35-COMMON-Pad1)") (class "Default")
      (node (ref "P35") (pin "1") (pinfunction "COMMON_1") (pintype "passive"))
    )
    (net (code "108") (name "unconnected-(P35-NO-Pad2)") (class "Default")
      (node (ref "P35") (pin "2") (pinfunction "NO_2") (pintype "passive"))
    )
    (net (code "109") (name "unconnected-(R15-Pad2)") (class "Default")
      (node (ref "R15") (pin "2") (pinfunction "2_2") (pintype "passive"))
    )
    (net (code "110") (name "unconnected-(RST1-COMMON-Pad1)") (class "Default")
      (node (ref "RST1") (pin "1") (pinfunction "COMMON_1") (pintype "passive"))
    )
    (net (code "111") (name "unconnected-(RST1-NO-Pad2)") (class "Default")
      (node (ref "RST1") (pin "2") (pinfunction "NO_2") (pintype "passive"))
    )
    (net (code "112") (name "unconnected-(S1-Pad1)") (class "Default")
      (node (ref "S1") (pin "1") (pinfunction "1_1") (pintype "passive"))
    )
    (net (code "113") (name "unconnected-(S1-Pad2)") (class "Default")
      (node (ref "S1") (pin "2") (pinfunction "2_2") (pintype "passive"))
    )
    (net (code "114") (name "unconnected-(S1-Pad3)") (class "Default")
      (node (ref "S1") (pin "3") (pinfunction "3_3") (pintype "passive"))
    )
  )
)
